# Adafruit_MCP73871_Solar_Charger_v4.net
KiCad netlist of a schematic drawn in EAGLE
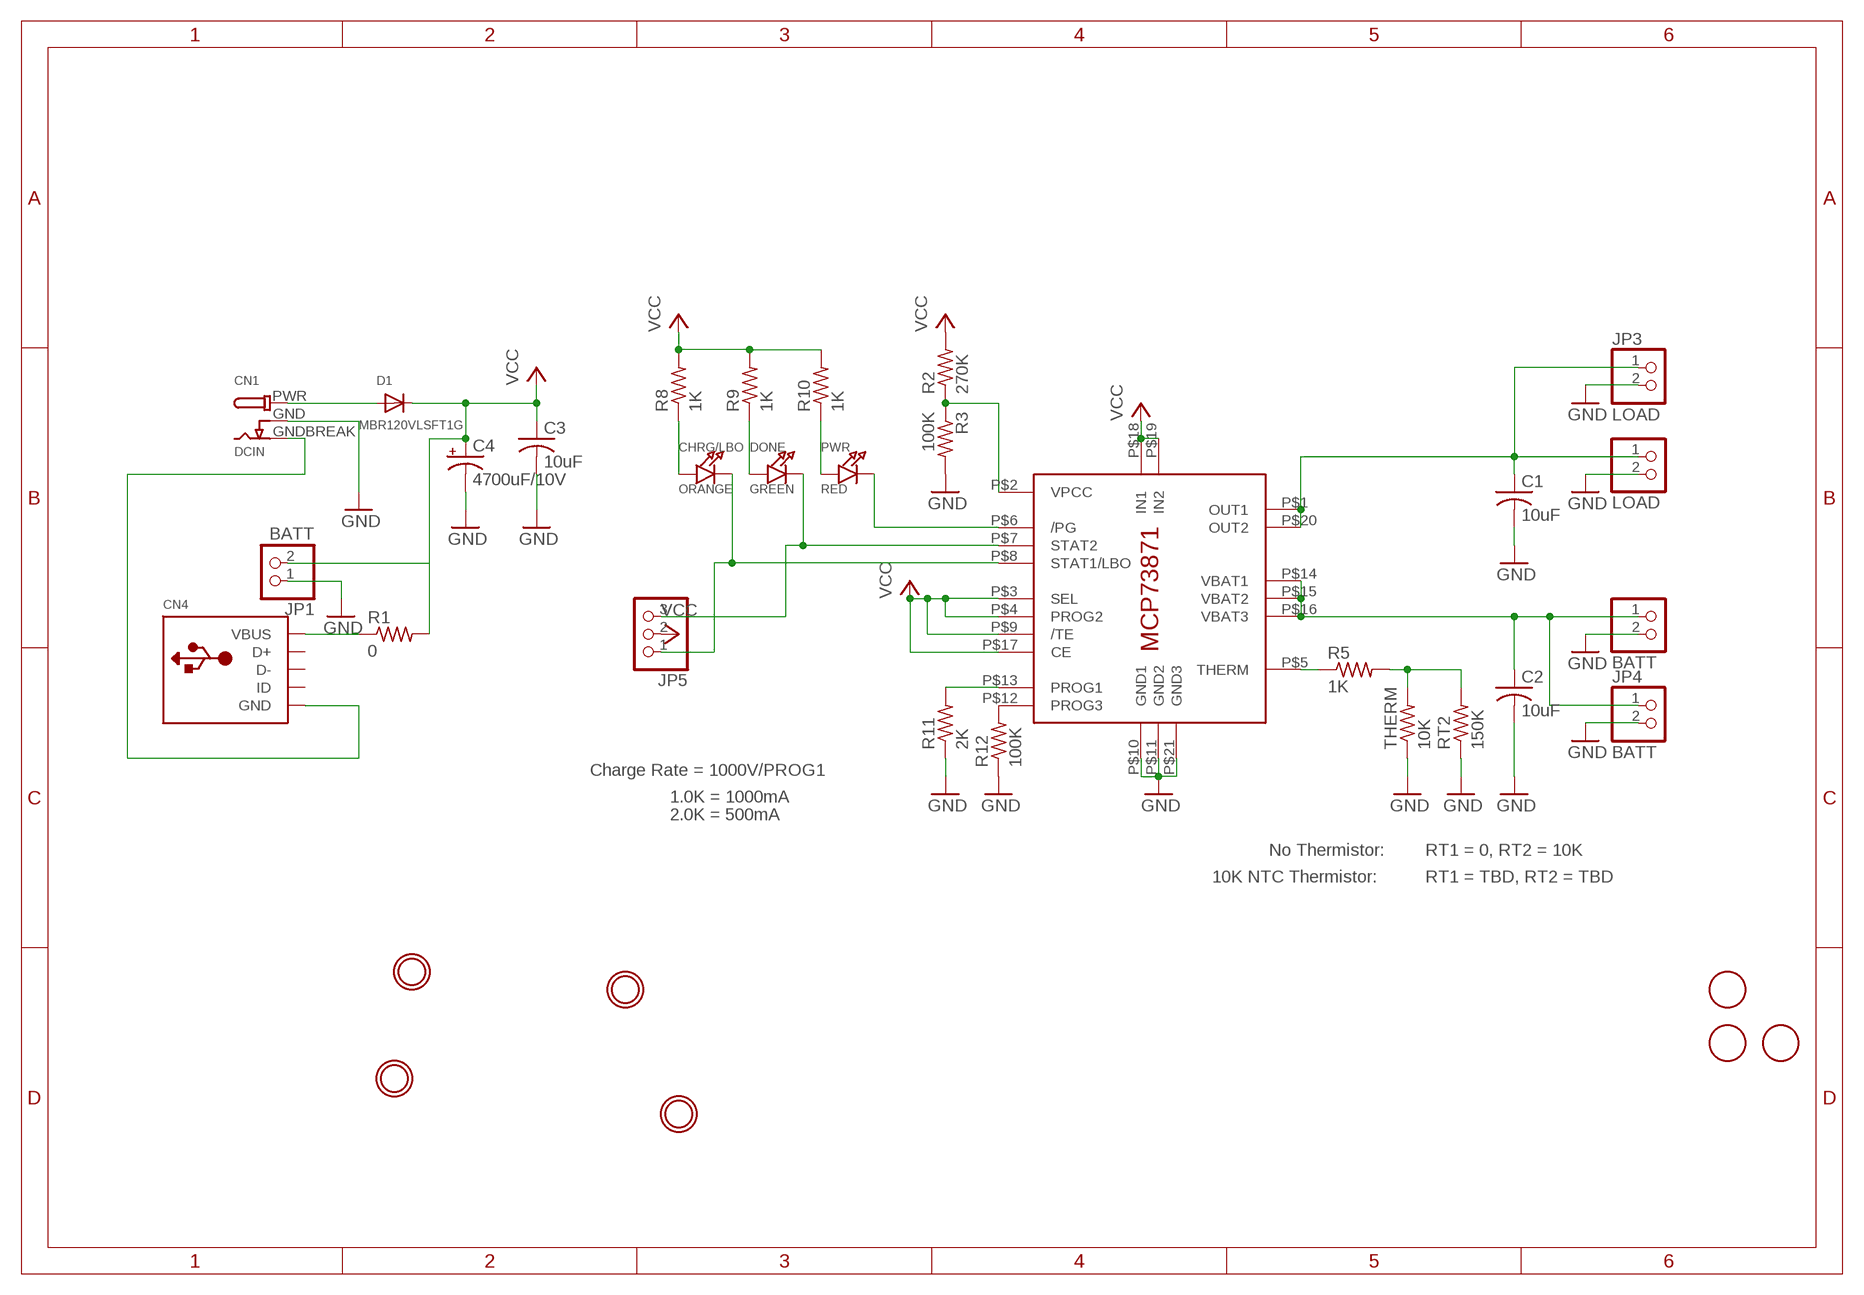
[diagram p0: schematic, sheet 1]

(export (version "E")
  (design (tool "Eeschema 10.0.6"))
  (components
    (comp (ref "BATT")
      (value "JST_2PIN-SMT-RA")
      (footprint "eagle-import:JST-PH-2-SMT-RA")
      (libsource (lib "eagle-import") (part "JST_2PIN-SMT-RA"))
    )
    (comp (ref "C1")
      (value "10uF")
      (footprint "eagle-import:C0805K")
      (libsource (lib "eagle-import") (part "C-USC0805K"))
    )
    (comp (ref "C2")
      (value "10uF")
      (footprint "eagle-import:C0805K")
      (libsource (lib "eagle-import") (part "C-USC0805K"))
    )
    (comp (ref "C3")
      (value "10uF")
      (footprint "eagle-import:C0805K")
      (libsource (lib "eagle-import") (part "C-USC0805K"))
    )
    (comp (ref "C4")
      (value "4700uF/10V")
      (footprint "eagle-import:E5-13")
      (libsource (lib "eagle-import") (part "CPOL-USE5-13"))
    )
    (comp (ref "CHRG/LBO")
      (value "ORANGE")
      (footprint "eagle-import:CHIPLED_0805_NOOUTLINE")
      (libsource (lib "eagle-import") (part "LED0805_NOOUTLINE"))
    )
    (comp (ref "CN1")
      (value "DCIN")
      (footprint "eagle-import:DCJACK_2MM_SMT")
      (libsource (lib "eagle-import") (part "DCBARRELSMT"))
    )
    (comp (ref "CN4")
      (value "USBMINIBLARGE")
      (footprint "eagle-import:USB-MINIB_LARGER")
      (libsource (lib "eagle-import") (part "USBMINIBLARGE"))
    )
    (comp (ref "D1")
      (value "MBR120VLSFT1G")
      (footprint "eagle-import:SOD-123")
      (libsource (lib "eagle-import") (part "DIODESOD-123"))
    )
    (comp (ref "DONE")
      (value "GREEN")
      (footprint "eagle-import:CHIPLED_0805_NOOUTLINE")
      (libsource (lib "eagle-import") (part "LED0805_NOOUTLINE"))
    )
    (comp (ref "JP1")
      (value "BATT")
      (footprint "eagle-import:1X02_ROUND")
      (libsource (lib "eagle-import") (part "HEADER-1X2ROUND"))
    )
    (comp (ref "JP3")
      (value "LOAD")
      (footprint "eagle-import:1X02_ROUND")
      (libsource (lib "eagle-import") (part "HEADER-1X2ROUND"))
    )
    (comp (ref "JP4")
      (value "BATT")
      (footprint "eagle-import:1X02_ROUND")
      (libsource (lib "eagle-import") (part "HEADER-1X2ROUND"))
    )
    (comp (ref "JP5")
      (value "PINHD-1X3CB")
      (footprint "eagle-import:1X03-CLEANBIG")
      (libsource (lib "eagle-import") (part "PINHD-1X3CB"))
    )
    (comp (ref "LOAD")
      (value "JST_2PIN-SMT-RA")
      (footprint "eagle-import:JST-PH-2-SMT-RA")
      (libsource (lib "eagle-import") (part "JST_2PIN-SMT-RA"))
    )
    (comp (ref "PWR")
      (value "RED")
      (footprint "eagle-import:CHIPLED_0805_NOOUTLINE")
      (libsource (lib "eagle-import") (part "LED0805_NOOUTLINE"))
    )
    (comp (ref "R1")
      (value "0")
      (footprint "eagle-import:R0805")
      (libsource (lib "eagle-import") (part "R-US_R0805"))
    )
    (comp (ref "R2")
      (value "270K")
      (footprint "eagle-import:R0805")
      (libsource (lib "eagle-import") (part "R-US_R0805"))
    )
    (comp (ref "R3")
      (value "100K")
      (footprint "eagle-import:R0805")
      (libsource (lib "eagle-import") (part "R-US_R0805"))
    )
    (comp (ref "R5")
      (value "1K")
      (footprint "eagle-import:M0805")
      (libsource (lib "eagle-import") (part "R-US_M0805"))
    )
    (comp (ref "R8")
      (value "1K")
      (footprint "eagle-import:R0805")
      (libsource (lib "eagle-import") (part "R-US_R0805"))
    )
    (comp (ref "R9")
      (value "1K")
      (footprint "eagle-import:R0805")
      (libsource (lib "eagle-import") (part "R-US_R0805"))
    )
    (comp (ref "R10")
      (value "1K")
      (footprint "eagle-import:R0805")
      (libsource (lib "eagle-import") (part "R-US_R0805"))
    )
    (comp (ref "R11")
      (value "2K")
      (footprint "eagle-import:0805-THM")
      (libsource (lib "eagle-import") (part "R-US_FLIPFLOP"))
    )
    (comp (ref "R12")
      (value "100K")
      (footprint "eagle-import:R0805")
      (libsource (lib "eagle-import") (part "R-US_R0805"))
    )
    (comp (ref "RT2")
      (value "150K")
      (footprint "eagle-import:M0805")
      (libsource (lib "eagle-import") (part "R-US_M0805"))
    )
    (comp (ref "THERM")
      (value "10K")
      (footprint "eagle-import:0805-THM")
      (libsource (lib "eagle-import") (part "R-US_FLIPFLOP"))
    )
    (comp (ref "U$2")
      (value "FIDUCIAL")
      (footprint "eagle-import:FIDUCIAL_1MM")
      (libsource (lib "eagle-import") (part "FIDUCIAL"))
    )
    (comp (ref "U$3")
      (value "FIDUCIAL")
      (footprint "eagle-import:FIDUCIAL_1MM")
      (libsource (lib "eagle-import") (part "FIDUCIAL"))
    )
    (comp (ref "U$4")
      (value "MOUNTINGHOLE2.5")
      (footprint "eagle-import:MOUNTINGHOLE_2.5_PLATED")
      (libsource (lib "eagle-import") (part "MOUNTINGHOLE2.5"))
    )
    (comp (ref "U$5")
      (value "MOUNTINGHOLE2.5")
      (footprint "eagle-import:MOUNTINGHOLE_2.5_PLATED")
      (libsource (lib "eagle-import") (part "MOUNTINGHOLE2.5"))
    )
    (comp (ref "U$6")
      (value "MOUNTINGHOLE2.5")
      (footprint "eagle-import:MOUNTINGHOLE_2.5_PLATED")
      (libsource (lib "eagle-import") (part "MOUNTINGHOLE2.5"))
    )
    (comp (ref "U$7")
      (value "MOUNTINGHOLE2.5")
      (footprint "eagle-import:MOUNTINGHOLE_2.5_PLATED")
      (libsource (lib "eagle-import") (part "MOUNTINGHOLE2.5"))
    )
    (comp (ref "U$8")
      (value "FIDUCIAL")
      (footprint "eagle-import:FIDUCIAL_1MM")
      (libsource (lib "eagle-import") (part "FIDUCIAL"))
    )
    (comp (ref "U1")
      (value "MCP73871")
      (footprint "eagle-import:QFN20_4MM")
      (libsource (lib "eagle-import") (part "MCP73871"))
    )
  )
  (nets
    (net (code "1") (name "GND") (class "Default")
      (node (ref "BATT") (pin "2") (pinfunction "1_2") (pintype "passive"))
      (node (ref "C1") (pin "2") (pinfunction "2_2") (pintype "passive"))
      (node (ref "C2") (pin "2") (pinfunction "2_2") (pintype "passive"))
      (node (ref "C3") (pin "2") (pinfunction "2_2") (pintype "passive"))
      (node (ref "C4") (pin "-") (pinfunction "-_-") (pintype "passive"))
      (node (ref "CN1") (pin "GND") (pinfunction "GNDBREAK_GND") (pintype "power_in"))
      (node (ref "JP1") (pin "1") (pinfunction "1_1") (pintype "passive"))
      (node (ref "JP3") (pin "2") (pinfunction "2_2") (pintype "passive"))
      (node (ref "JP4") (pin "2") (pinfunction "2_2") (pintype "passive"))
      (node (ref "LOAD") (pin "2") (pinfunction "1_2") (pintype "passive"))
      (node (ref "R11") (pin "1") (pinfunction "1_1") (pintype "passive"))
      (node (ref "R12") (pin "1") (pinfunction "1_1") (pintype "passive"))
      (node (ref "R3") (pin "2") (pinfunction "2_2") (pintype "passive"))
      (node (ref "RT2") (pin "1") (pinfunction "1_1") (pintype "passive"))
      (node (ref "THERM") (pin "1") (pinfunction "1_1") (pintype "passive"))
      (node (ref "U1") (pin "P$10") (pinfunction "GND1_P$10") (pintype "power_in"))
      (node (ref "U1") (pin "P$11") (pinfunction "GND2_P$11") (pintype "power_in"))
      (node (ref "U1") (pin "P$21") (pinfunction "GND3_P$21") (pintype "power_in"))
    )
    (net (code "2") (name "Net-(BATT-2)") (class "Default")
      (node (ref "BATT") (pin "1") (pinfunction "2_1") (pintype "passive"))
      (node (ref "C2") (pin "1") (pinfunction "1_1") (pintype "passive"))
      (node (ref "JP4") (pin "1") (pinfunction "1_1") (pintype "passive"))
      (node (ref "U1") (pin "P$14") (pinfunction "VBAT1_P$14") (pintype "output"))
      (node (ref "U1") (pin "P$15") (pinfunction "VBAT2_P$15") (pintype "output"))
      (node (ref "U1") (pin "P$16") (pinfunction "VBAT3_P$16") (pintype "output"))
    )
    (net (code "3") (name "Net-(CHRG/LBO-PadA)") (class "Default")
      (node (ref "CHRG/LBO") (pin "A") (pinfunction "A_A") (pintype "passive"))
      (node (ref "R8") (pin "1") (pinfunction "1_1") (pintype "passive"))
    )
    (net (code "4") (name "Net-(CN1-GND)") (class "Default")
      (node (ref "CN1") (pin "GNDBREAK") (pinfunction "GND_GNDBREAK") (pintype "power_in"))
      (node (ref "CN4") (pin "GND") (pinfunction "GND_GND") (pintype "power_in"))
      (node (ref "CN4") (pin "GND1") (pinfunction "GND_GND1") (pintype "power_in"))
      (node (ref "CN4") (pin "GND2") (pinfunction "GND_GND2") (pintype "power_in"))
      (node (ref "CN4") (pin "GND3") (pinfunction "GND_GND3") (pintype "power_in"))
      (node (ref "CN4") (pin "GND4") (pinfunction "GND_GND4") (pintype "power_in"))
    )
    (net (code "5") (name "Net-(CN1-PadPWR)") (class "Default")
      (node (ref "CN1") (pin "PWR") (pinfunction "PWR_PWR") (pintype "power_in"))
      (node (ref "D1") (pin "A") (pinfunction "A_A") (pintype "passive"))
    )
    (net (code "6") (name "Net-(CN4-PadVBUS)") (class "Default")
      (node (ref "CN4") (pin "VBUS") (pinfunction "VBUS_VBUS") (pintype "power_in"))
      (node (ref "R1") (pin "1") (pinfunction "1_1") (pintype "passive"))
    )
    (net (code "7") (name "Net-(DONE-PadA)") (class "Default")
      (node (ref "DONE") (pin "A") (pinfunction "A_A") (pintype "passive"))
      (node (ref "R9") (pin "1") (pinfunction "1_1") (pintype "passive"))
    )
    (net (code "8") (name "Net-(LOAD-2)") (class "Default")
      (node (ref "C1") (pin "1") (pinfunction "1_1") (pintype "passive"))
      (node (ref "JP3") (pin "1") (pinfunction "1_1") (pintype "passive"))
      (node (ref "LOAD") (pin "1") (pinfunction "2_1") (pintype "passive"))
      (node (ref "U1") (pin "P$1") (pinfunction "OUT1_P$1") (pintype "output"))
      (node (ref "U1") (pin "P$20") (pinfunction "OUT2_P$20") (pintype "output"))
    )
    (net (code "9") (name "Net-(PWR-PadA)") (class "Default")
      (node (ref "PWR") (pin "A") (pinfunction "A_A") (pintype "passive"))
      (node (ref "R10") (pin "1") (pinfunction "1_1") (pintype "passive"))
    )
    (net (code "10") (name "Net-(R5-Pad2)") (class "Default")
      (node (ref "R5") (pin "2") (pinfunction "2_2") (pintype "passive"))
      (node (ref "RT2") (pin "2") (pinfunction "2_2") (pintype "passive"))
      (node (ref "THERM") (pin "2") (pinfunction "2_2") (pintype "passive"))
    )
    (net (code "11") (name "Net-(U1-PROG1)") (class "Default")
      (node (ref "R11") (pin "2") (pinfunction "2_2") (pintype "passive"))
      (node (ref "U1") (pin "P$13") (pinfunction "PROG1_P$13") (pintype "input"))
    )
    (net (code "12") (name "Net-(U1-PROG3)") (class "Default")
      (node (ref "R12") (pin "2") (pinfunction "2_2") (pintype "passive"))
      (node (ref "U1") (pin "P$12") (pinfunction "PROG3_P$12") (pintype "input"))
    )
    (net (code "13") (name "Net-(U1-STAT1{slash}LBO)") (class "Default")
      (node (ref "CHRG/LBO") (pin "C") (pinfunction "C_C") (pintype "passive"))
      (node (ref "JP5") (pin "1") (pinfunction "1_1") (pintype "passive"))
      (node (ref "U1") (pin "P$8") (pinfunction "STAT1/LBO_P$8") (pintype "output"))
    )
    (net (code "14") (name "Net-(U1-STAT2)") (class "Default")
      (node (ref "DONE") (pin "C") (pinfunction "C_C") (pintype "passive"))
      (node (ref "JP5") (pin "3") (pinfunction "3_3") (pintype "passive"))
      (node (ref "U1") (pin "P$7") (pinfunction "STAT2_P$7") (pintype "output"))
    )
    (net (code "15") (name "Net-(U1-THERM)") (class "Default")
      (node (ref "R5") (pin "1") (pinfunction "1_1") (pintype "passive"))
      (node (ref "U1") (pin "P$5") (pinfunction "THERM_P$5") (pintype "input"))
    )
    (net (code "16") (name "Net-(U1-VPCC)") (class "Default")
      (node (ref "R2") (pin "1") (pinfunction "1_1") (pintype "passive"))
      (node (ref "R3") (pin "1") (pinfunction "1_1") (pintype "passive"))
      (node (ref "U1") (pin "P$2") (pinfunction "VPCC_P$2") (pintype "input"))
    )
    (net (code "17") (name "Net-(U1-{slash}PG)") (class "Default")
      (node (ref "PWR") (pin "C") (pinfunction "C_C") (pintype "passive"))
      (node (ref "U1") (pin "P$6") (pinfunction "/PG_P$6") (pintype "output"))
    )
    (net (code "18") (name "VCC") (class "Default")
      (node (ref "C3") (pin "1") (pinfunction "1_1") (pintype "passive"))
      (node (ref "C4") (pin "+") (pinfunction "+_+") (pintype "passive"))
      (node (ref "D1") (pin "C") (pinfunction "C_C") (pintype "passive"))
      (node (ref "JP1") (pin "2") (pinfunction "2_2") (pintype "passive"))
      (node (ref "JP5") (pin "2") (pinfunction "2_2") (pintype "passive"))
      (node (ref "R1") (pin "2") (pinfunction "2_2") (pintype "passive"))
      (node (ref "R10") (pin "2") (pinfunction "2_2") (pintype "passive"))
      (node (ref "R2") (pin "2") (pinfunction "2_2") (pintype "passive"))
      (node (ref "R8") (pin "2") (pinfunction "2_2") (pintype "passive"))
      (node (ref "R9") (pin "2") (pinfunction "2_2") (pintype "passive"))
      (node (ref "U1") (pin "P$17") (pinfunction "CE_P$17") (pintype "input"))
      (node (ref "U1") (pin "P$18") (pinfunction "IN1_P$18") (pintype "input"))
      (node (ref "U1") (pin "P$19") (pinfunction "IN2_P$19") (pintype "input"))
      (node (ref "U1") (pin "P$3") (pinfunction "SEL_P$3") (pintype "input"))
      (node (ref "U1") (pin "P$4") (pinfunction "PROG2_P$4") (pintype "input"))
      (node (ref "U1") (pin "P$9") (pinfunction "/TE_P$9") (pintype "input"))
    )
    (net (code "19") (name "unconnected-(CN4-PadD+)") (class "Default")
      (node (ref "CN4") (pin "D+") (pinfunction "D+_D+") (pintype "bidirectional"))
    )
    (net (code "20") (name "unconnected-(CN4-PadD-)") (class "Default")
      (node (ref "CN4") (pin "D-") (pinfunction "D-_D-") (pintype "bidirectional"))
    )
    (net (code "21") (name "unconnected-(CN4-PadID)") (class "Default")
      (node (ref "CN4") (pin "ID") (pinfunction "ID_ID") (pintype "bidirectional"))
    )
  )
)
